# Break_Light_Schematic.net
KiCad netlist of a schematic drawn in Altium Designer
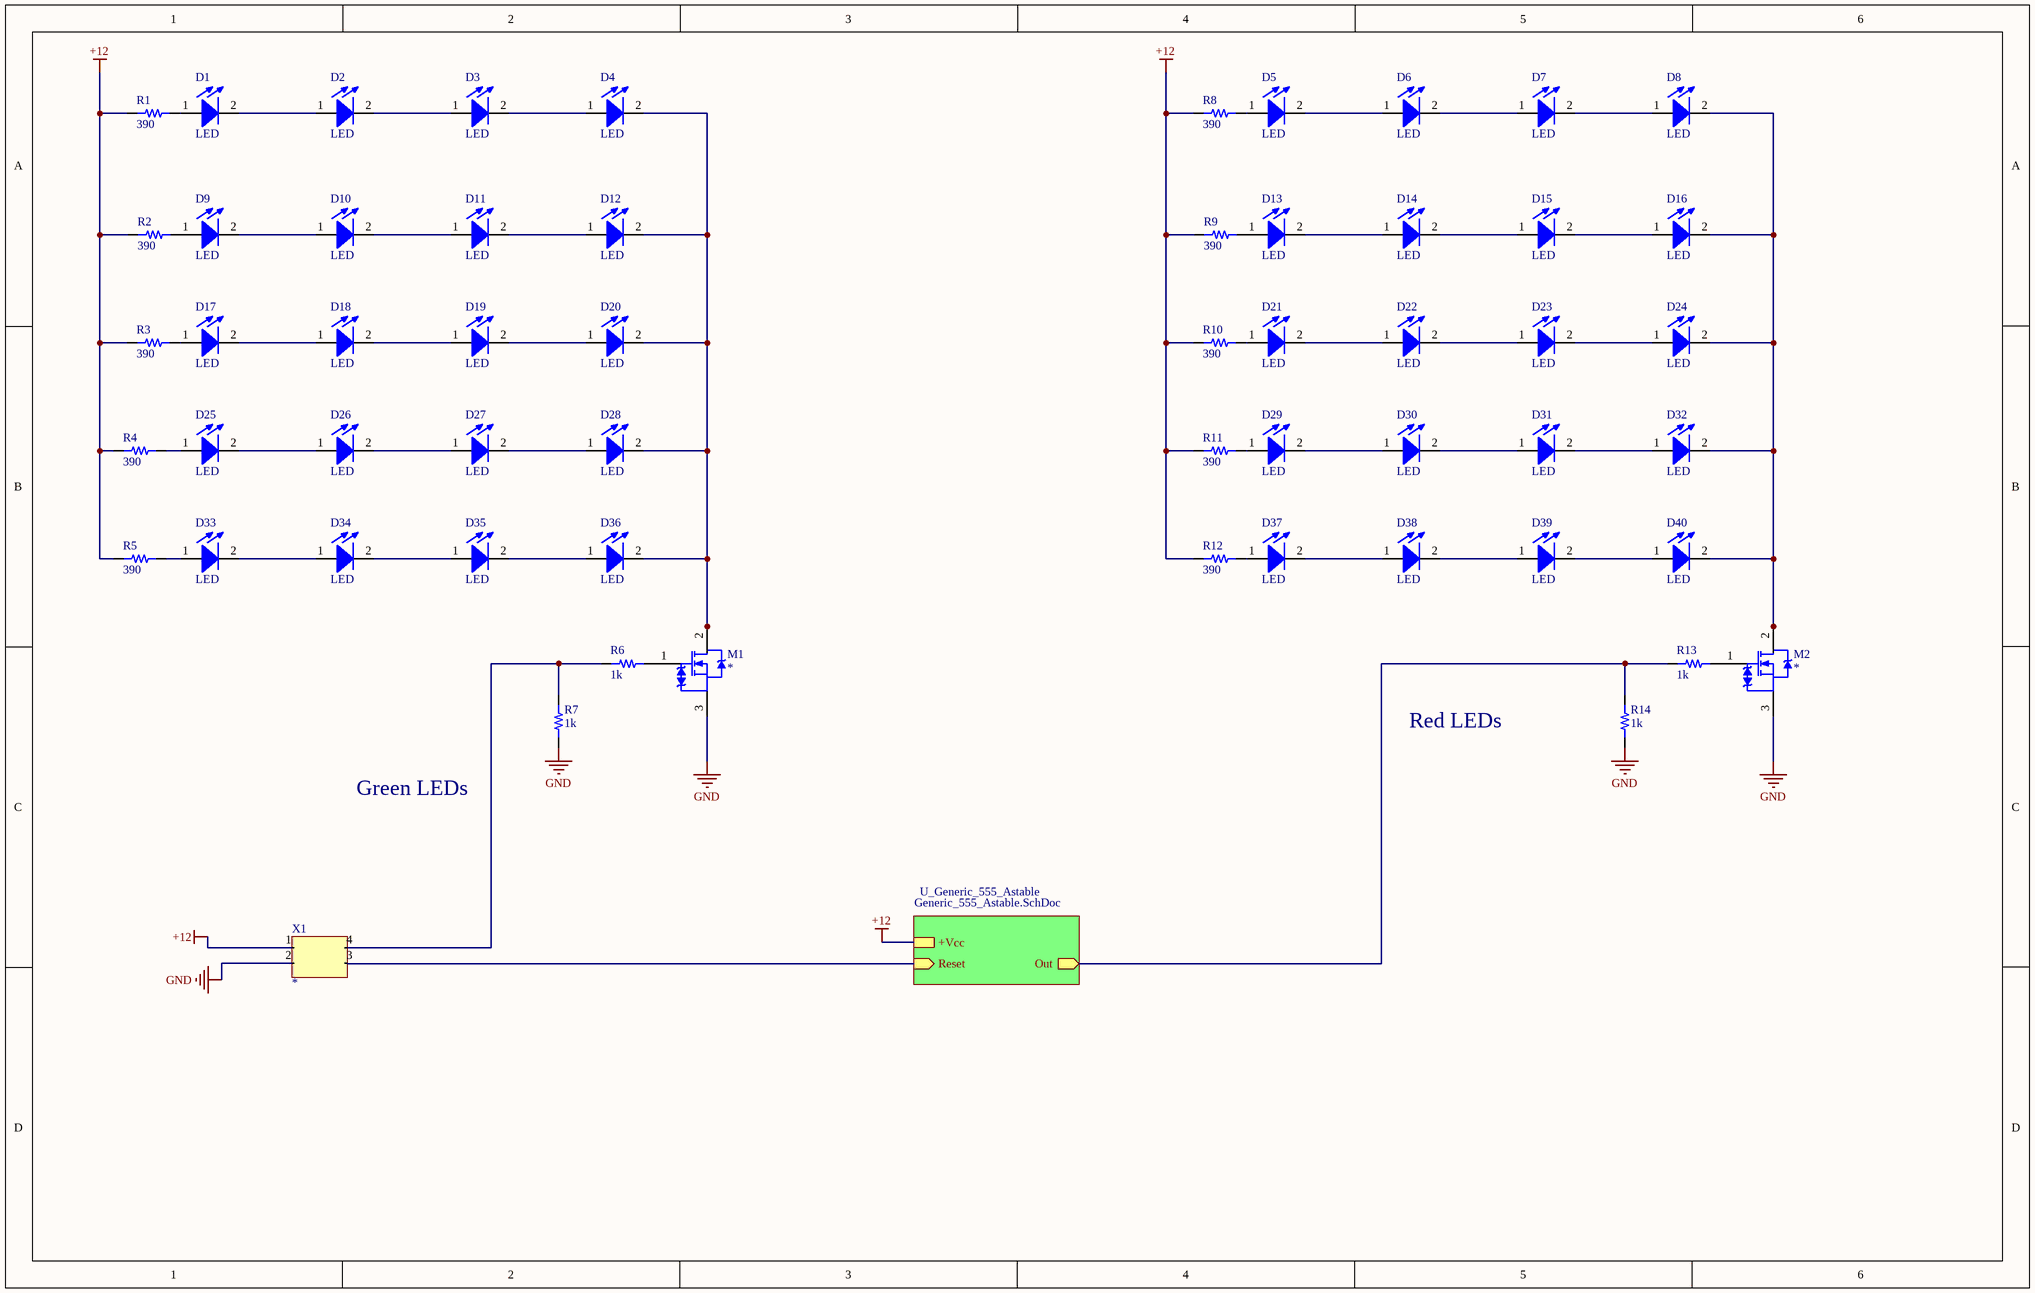
[diagram p0: Break Light Schematic.SchDoc]

(export (version "E")
  (design (tool "Eeschema 10.0.6"))
  (components
    (comp (ref "D1")
      (value "LED")
      (footprint "LED TH")
      (description "Thru Hole LED")
      (libsource (lib "altlib") (part "LED"))
    )
    (comp (ref "D2")
      (value "LED")
      (footprint "LED TH")
      (description "Thru Hole LED")
      (libsource (lib "altlib") (part "LED"))
    )
    (comp (ref "D3")
      (value "LED")
      (footprint "LED TH")
      (description "Thru Hole LED")
      (libsource (lib "altlib") (part "LED"))
    )
    (comp (ref "D4")
      (value "LED")
      (footprint "LED TH")
      (description "Thru Hole LED")
      (libsource (lib "altlib") (part "LED"))
    )
    (comp (ref "D5")
      (value "LED")
      (footprint "LED TH")
      (description "Thru Hole LED")
      (libsource (lib "altlib") (part "LED"))
    )
    (comp (ref "D6")
      (value "LED")
      (footprint "LED TH")
      (description "Thru Hole LED")
      (libsource (lib "altlib") (part "LED"))
    )
    (comp (ref "D7")
      (value "LED")
      (footprint "LED TH")
      (description "Thru Hole LED")
      (libsource (lib "altlib") (part "LED"))
    )
    (comp (ref "D8")
      (value "LED")
      (footprint "LED TH")
      (description "Thru Hole LED")
      (libsource (lib "altlib") (part "LED"))
    )
    (comp (ref "D9")
      (value "LED")
      (footprint "LED TH")
      (description "Thru Hole LED")
      (libsource (lib "altlib") (part "LED"))
    )
    (comp (ref "D10")
      (value "LED")
      (footprint "LED TH")
      (description "Thru Hole LED")
      (libsource (lib "altlib") (part "LED"))
    )
    (comp (ref "D11")
      (value "LED")
      (footprint "LED TH")
      (description "Thru Hole LED")
      (libsource (lib "altlib") (part "LED"))
    )
    (comp (ref "D12")
      (value "LED")
      (footprint "LED TH")
      (description "Thru Hole LED")
      (libsource (lib "altlib") (part "LED"))
    )
    (comp (ref "D13")
      (value "LED")
      (footprint "LED TH")
      (description "Thru Hole LED")
      (libsource (lib "altlib") (part "LED"))
    )
    (comp (ref "D14")
      (value "LED")
      (footprint "LED TH")
      (description "Thru Hole LED")
      (libsource (lib "altlib") (part "LED"))
    )
    (comp (ref "D15")
      (value "LED")
      (footprint "LED TH")
      (description "Thru Hole LED")
      (libsource (lib "altlib") (part "LED"))
    )
    (comp (ref "D16")
      (value "LED")
      (footprint "LED TH")
      (description "Thru Hole LED")
      (libsource (lib "altlib") (part "LED"))
    )
    (comp (ref "D17")
      (value "LED")
      (footprint "LED TH")
      (description "Thru Hole LED")
      (libsource (lib "altlib") (part "LED"))
    )
    (comp (ref "D18")
      (value "LED")
      (footprint "LED TH")
      (description "Thru Hole LED")
      (libsource (lib "altlib") (part "LED"))
    )
    (comp (ref "D19")
      (value "LED")
      (footprint "LED TH")
      (description "Thru Hole LED")
      (libsource (lib "altlib") (part "LED"))
    )
    (comp (ref "D20")
      (value "LED")
      (footprint "LED TH")
      (description "Thru Hole LED")
      (libsource (lib "altlib") (part "LED"))
    )
    (comp (ref "D21")
      (value "LED")
      (footprint "LED TH")
      (description "Thru Hole LED")
      (libsource (lib "altlib") (part "LED"))
    )
    (comp (ref "D22")
      (value "LED")
      (footprint "LED TH")
      (description "Thru Hole LED")
      (libsource (lib "altlib") (part "LED"))
    )
    (comp (ref "D23")
      (value "LED")
      (footprint "LED TH")
      (description "Thru Hole LED")
      (libsource (lib "altlib") (part "LED"))
    )
    (comp (ref "D24")
      (value "LED")
      (footprint "LED TH")
      (description "Thru Hole LED")
      (libsource (lib "altlib") (part "LED"))
    )
    (comp (ref "D25")
      (value "LED")
      (footprint "LED TH")
      (description "Thru Hole LED")
      (libsource (lib "altlib") (part "LED"))
    )
    (comp (ref "D26")
      (value "LED")
      (footprint "LED TH")
      (description "Thru Hole LED")
      (libsource (lib "altlib") (part "LED"))
    )
    (comp (ref "D27")
      (value "LED")
      (footprint "LED TH")
      (description "Thru Hole LED")
      (libsource (lib "altlib") (part "LED"))
    )
    (comp (ref "D28")
      (value "LED")
      (footprint "LED TH")
      (description "Thru Hole LED")
      (libsource (lib "altlib") (part "LED"))
    )
    (comp (ref "D29")
      (value "LED")
      (footprint "LED TH")
      (description "Thru Hole LED")
      (libsource (lib "altlib") (part "LED"))
    )
    (comp (ref "D30")
      (value "LED")
      (footprint "LED TH")
      (description "Thru Hole LED")
      (libsource (lib "altlib") (part "LED"))
    )
    (comp (ref "D31")
      (value "LED")
      (footprint "LED TH")
      (description "Thru Hole LED")
      (libsource (lib "altlib") (part "LED"))
    )
    (comp (ref "D32")
      (value "LED")
      (footprint "LED TH")
      (description "Thru Hole LED")
      (libsource (lib "altlib") (part "LED"))
    )
    (comp (ref "D33")
      (value "LED")
      (footprint "LED TH")
      (description "Thru Hole LED")
      (libsource (lib "altlib") (part "LED"))
    )
    (comp (ref "D34")
      (value "LED")
      (footprint "LED TH")
      (description "Thru Hole LED")
      (libsource (lib "altlib") (part "LED"))
    )
    (comp (ref "D35")
      (value "LED")
      (footprint "LED TH")
      (description "Thru Hole LED")
      (libsource (lib "altlib") (part "LED"))
    )
    (comp (ref "D36")
      (value "LED")
      (footprint "LED TH")
      (description "Thru Hole LED")
      (libsource (lib "altlib") (part "LED"))
    )
    (comp (ref "D37")
      (value "LED")
      (footprint "LED TH")
      (description "Thru Hole LED")
      (libsource (lib "altlib") (part "LED"))
    )
    (comp (ref "D38")
      (value "LED")
      (footprint "LED TH")
      (description "Thru Hole LED")
      (libsource (lib "altlib") (part "LED"))
    )
    (comp (ref "D39")
      (value "LED")
      (footprint "LED TH")
      (description "Thru Hole LED")
      (libsource (lib "altlib") (part "LED"))
    )
    (comp (ref "D40")
      (value "LED")
      (footprint "LED TH")
      (description "Thru Hole LED")
      (libsource (lib "altlib") (part "LED"))
    )
    (comp (ref "M1")
      (value "*")
      (footprint "SOT-223-3")
      (description "N-Channel 450V 600mA (Tc) 3W (Ta) Surface Mo")
      (libsource (lib "altlib") (part "STN3N45K3"))
    )
    (comp (ref "M2")
      (value "*")
      (footprint "SOT-223-3")
      (description "N-Channel 450V 600mA (Tc) 3W (Ta) Surface Mo")
      (libsource (lib "altlib") (part "STN3N45K3"))
    )
    (comp (ref "R1")
      (value "390")
      (footprint "RES 0603/1608")
      (fields (field (name "RESISTANCE") "390"))
      (libsource (lib "altlib") (part "Resistor"))
    )
    (comp (ref "R2")
      (value "390")
      (footprint "RES 0603/1608")
      (fields (field (name "RESISTANCE") "390"))
      (libsource (lib "altlib") (part "Resistor"))
    )
    (comp (ref "R3")
      (value "390")
      (footprint "RES 0603/1608")
      (fields (field (name "RESISTANCE") "390"))
      (libsource (lib "altlib") (part "Resistor"))
    )
    (comp (ref "R4")
      (value "390")
      (footprint "RES 0603/1608")
      (fields (field (name "RESISTANCE") "390"))
      (libsource (lib "altlib") (part "Resistor"))
    )
    (comp (ref "R5")
      (value "390")
      (footprint "RES 0603/1608")
      (fields (field (name "RESISTANCE") "390"))
      (libsource (lib "altlib") (part "Resistor"))
    )
    (comp (ref "R6")
      (value "1k")
      (footprint "RES 0603/1608")
      (fields (field (name "RESISTANCE") "1k"))
      (libsource (lib "altlib") (part "Resistor"))
    )
    (comp (ref "R7")
      (value "1k")
      (footprint "RES 0603/1608")
      (fields (field (name "RESISTANCE") "1k"))
      (libsource (lib "altlib") (part "Resistor"))
    )
    (comp (ref "R8")
      (value "390")
      (footprint "RES 0603/1608")
      (fields (field (name "RESISTANCE") "390"))
      (libsource (lib "altlib") (part "Resistor"))
    )
    (comp (ref "R9")
      (value "390")
      (footprint "RES 0603/1608")
      (fields (field (name "RESISTANCE") "390"))
      (libsource (lib "altlib") (part "Resistor"))
    )
    (comp (ref "R10")
      (value "390")
      (footprint "RES 0603/1608")
      (fields (field (name "RESISTANCE") "390"))
      (libsource (lib "altlib") (part "Resistor"))
    )
    (comp (ref "R11")
      (value "390")
      (footprint "RES 0603/1608")
      (fields (field (name "RESISTANCE") "390"))
      (libsource (lib "altlib") (part "Resistor"))
    )
    (comp (ref "R12")
      (value "390")
      (footprint "RES 0603/1608")
      (fields (field (name "RESISTANCE") "390"))
      (libsource (lib "altlib") (part "Resistor"))
    )
    (comp (ref "R13")
      (value "1k")
      (footprint "RES 0603/1608")
      (fields (field (name "RESISTANCE") "1k"))
      (libsource (lib "altlib") (part "Resistor"))
    )
    (comp (ref "R14")
      (value "1k")
      (footprint "RES 0603/1608")
      (fields (field (name "RESISTANCE") "1k"))
      (libsource (lib "altlib") (part "Resistor"))
    )
    (comp (ref "X1")
      (value "*")
      (footprint "DT15-4P")
      (description "DT15-4P Connector for Brakelight")
      (fields (field (name "CREATEDBY") "Andrew"))
      (libsource (lib "altlib") (part "CONN 4POS"))
    )
  )
  (nets
    (net (code "1") (name "+12") (class "Default")
      (node (ref "R1") (pin "1") (pinfunction "1_1") (pintype "passive"))
      (node (ref "R10") (pin "1") (pinfunction "1_1") (pintype "passive"))
      (node (ref "R11") (pin "1") (pinfunction "1_1") (pintype "passive"))
      (node (ref "R12") (pin "1") (pinfunction "1_1") (pintype "passive"))
      (node (ref "R2") (pin "1") (pinfunction "1_1") (pintype "passive"))
      (node (ref "R3") (pin "1") (pinfunction "1_1") (pintype "passive"))
      (node (ref "R4") (pin "1") (pinfunction "1_1") (pintype "passive"))
      (node (ref "R5") (pin "1") (pinfunction "1_1") (pintype "passive"))
      (node (ref "R8") (pin "1") (pinfunction "1_1") (pintype "passive"))
      (node (ref "R9") (pin "1") (pinfunction "1_1") (pintype "passive"))
      (node (ref "X1") (pin "1") (pintype "input"))
    )
    (net (code "2") (name "/Out") (class "Default")
      (node (ref "R13") (pin "1") (pinfunction "1_1") (pintype "passive"))
      (node (ref "R14") (pin "2") (pinfunction "2_2") (pintype "passive"))
    )
    (net (code "3") (name "/Reset") (class "Default") (node (ref "X1") (pin "3") (pintype "bidirectional")))
    (net (code "4") (name "GND") (class "Default")
      (node (ref "M1") (pin "3") (pinfunction "S_3") (pintype "passive"))
      (node (ref "M2") (pin "3") (pinfunction "S_3") (pintype "passive"))
      (node (ref "R14") (pin "1") (pinfunction "1_1") (pintype "passive"))
      (node (ref "R7") (pin "1") (pinfunction "1_1") (pintype "passive"))
      (node (ref "X1") (pin "2") (pintype "input"))
    )
    (net (code "5") (name "Net-(D1-A)") (class "Default")
      (node (ref "D1") (pin "1") (pinfunction "A_1") (pintype "passive"))
      (node (ref "R1") (pin "2") (pinfunction "2_2") (pintype "passive"))
    )
    (net (code "6") (name "Net-(D1-K)") (class "Default")
      (node (ref "D1") (pin "2") (pinfunction "K_2") (pintype "passive"))
      (node (ref "D2") (pin "1") (pinfunction "A_1") (pintype "passive"))
    )
    (net (code "7") (name "Net-(D2-K)") (class "Default")
      (node (ref "D2") (pin "2") (pinfunction "K_2") (pintype "passive"))
      (node (ref "D3") (pin "1") (pinfunction "A_1") (pintype "passive"))
    )
    (net (code "8") (name "Net-(D3-K)") (class "Default")
      (node (ref "D3") (pin "2") (pinfunction "K_2") (pintype "passive"))
      (node (ref "D4") (pin "1") (pinfunction "A_1") (pintype "passive"))
    )
    (net (code "9") (name "Net-(D5-A)") (class "Default")
      (node (ref "D5") (pin "1") (pinfunction "A_1") (pintype "passive"))
      (node (ref "R8") (pin "2") (pinfunction "2_2") (pintype "passive"))
    )
    (net (code "10") (name "Net-(D5-K)") (class "Default")
      (node (ref "D5") (pin "2") (pinfunction "K_2") (pintype "passive"))
      (node (ref "D6") (pin "1") (pinfunction "A_1") (pintype "passive"))
    )
    (net (code "11") (name "Net-(D6-K)") (class "Default")
      (node (ref "D6") (pin "2") (pinfunction "K_2") (pintype "passive"))
      (node (ref "D7") (pin "1") (pinfunction "A_1") (pintype "passive"))
    )
    (net (code "12") (name "Net-(D7-K)") (class "Default")
      (node (ref "D7") (pin "2") (pinfunction "K_2") (pintype "passive"))
      (node (ref "D8") (pin "1") (pinfunction "A_1") (pintype "passive"))
    )
    (net (code "13") (name "Net-(D9-A)") (class "Default")
      (node (ref "D9") (pin "1") (pinfunction "A_1") (pintype "passive"))
      (node (ref "R2") (pin "2") (pinfunction "2_2") (pintype "passive"))
    )
    (net (code "14") (name "Net-(D10-A)") (class "Default")
      (node (ref "D10") (pin "1") (pinfunction "A_1") (pintype "passive"))
      (node (ref "D9") (pin "2") (pinfunction "K_2") (pintype "passive"))
    )
    (net (code "15") (name "Net-(D10-K)") (class "Default")
      (node (ref "D10") (pin "2") (pinfunction "K_2") (pintype "passive"))
      (node (ref "D11") (pin "1") (pinfunction "A_1") (pintype "passive"))
    )
    (net (code "16") (name "Net-(D11-K)") (class "Default")
      (node (ref "D11") (pin "2") (pinfunction "K_2") (pintype "passive"))
      (node (ref "D12") (pin "1") (pinfunction "A_1") (pintype "passive"))
    )
    (net (code "17") (name "Net-(D12-K)") (class "Default")
      (node (ref "D12") (pin "2") (pinfunction "K_2") (pintype "passive"))
      (node (ref "D20") (pin "2") (pinfunction "K_2") (pintype "passive"))
      (node (ref "D28") (pin "2") (pinfunction "K_2") (pintype "passive"))
      (node (ref "D36") (pin "2") (pinfunction "K_2") (pintype "passive"))
      (node (ref "D4") (pin "2") (pinfunction "K_2") (pintype "passive"))
      (node (ref "M1") (pin "2") (pinfunction "D_2") (pintype "passive"))
      (node (ref "M1") (pin "THM") (pinfunction "D_THM") (pintype "passive"))
    )
    (net (code "18") (name "Net-(D13-A)") (class "Default")
      (node (ref "D13") (pin "1") (pinfunction "A_1") (pintype "passive"))
      (node (ref "R9") (pin "2") (pinfunction "2_2") (pintype "passive"))
    )
    (net (code "19") (name "Net-(D13-K)") (class "Default")
      (node (ref "D13") (pin "2") (pinfunction "K_2") (pintype "passive"))
      (node (ref "D14") (pin "1") (pinfunction "A_1") (pintype "passive"))
    )
    (net (code "20") (name "Net-(D14-K)") (class "Default")
      (node (ref "D14") (pin "2") (pinfunction "K_2") (pintype "passive"))
      (node (ref "D15") (pin "1") (pinfunction "A_1") (pintype "passive"))
    )
    (net (code "21") (name "Net-(D15-K)") (class "Default")
      (node (ref "D15") (pin "2") (pinfunction "K_2") (pintype "passive"))
      (node (ref "D16") (pin "1") (pinfunction "A_1") (pintype "passive"))
    )
    (net (code "22") (name "Net-(D16-K)") (class "Default")
      (node (ref "D16") (pin "2") (pinfunction "K_2") (pintype "passive"))
      (node (ref "D24") (pin "2") (pinfunction "K_2") (pintype "passive"))
      (node (ref "D32") (pin "2") (pinfunction "K_2") (pintype "passive"))
      (node (ref "D40") (pin "2") (pinfunction "K_2") (pintype "passive"))
      (node (ref "D8") (pin "2") (pinfunction "K_2") (pintype "passive"))
      (node (ref "M2") (pin "2") (pinfunction "D_2") (pintype "passive"))
      (node (ref "M2") (pin "THM") (pinfunction "D_THM") (pintype "passive"))
    )
    (net (code "23") (name "Net-(D17-A)") (class "Default")
      (node (ref "D17") (pin "1") (pinfunction "A_1") (pintype "passive"))
      (node (ref "R3") (pin "2") (pinfunction "2_2") (pintype "passive"))
    )
    (net (code "24") (name "Net-(D17-K)") (class "Default")
      (node (ref "D17") (pin "2") (pinfunction "K_2") (pintype "passive"))
      (node (ref "D18") (pin "1") (pinfunction "A_1") (pintype "passive"))
    )
    (net (code "25") (name "Net-(D18-K)") (class "Default")
      (node (ref "D18") (pin "2") (pinfunction "K_2") (pintype "passive"))
      (node (ref "D19") (pin "1") (pinfunction "A_1") (pintype "passive"))
    )
    (net (code "26") (name "Net-(D19-K)") (class "Default")
      (node (ref "D19") (pin "2") (pinfunction "K_2") (pintype "passive"))
      (node (ref "D20") (pin "1") (pinfunction "A_1") (pintype "passive"))
    )
    (net (code "27") (name "Net-(D21-A)") (class "Default")
      (node (ref "D21") (pin "1") (pinfunction "A_1") (pintype "passive"))
      (node (ref "R10") (pin "2") (pinfunction "2_2") (pintype "passive"))
    )
    (net (code "28") (name "Net-(D21-K)") (class "Default")
      (node (ref "D21") (pin "2") (pinfunction "K_2") (pintype "passive"))
      (node (ref "D22") (pin "1") (pinfunction "A_1") (pintype "passive"))
    )
    (net (code "29") (name "Net-(D22-K)") (class "Default")
      (node (ref "D22") (pin "2") (pinfunction "K_2") (pintype "passive"))
      (node (ref "D23") (pin "1") (pinfunction "A_1") (pintype "passive"))
    )
    (net (code "30") (name "Net-(D23-K)") (class "Default")
      (node (ref "D23") (pin "2") (pinfunction "K_2") (pintype "passive"))
      (node (ref "D24") (pin "1") (pinfunction "A_1") (pintype "passive"))
    )
    (net (code "31") (name "Net-(D25-A)") (class "Default")
      (node (ref "D25") (pin "1") (pinfunction "A_1") (pintype "passive"))
      (node (ref "R4") (pin "2") (pinfunction "2_2") (pintype "passive"))
    )
    (net (code "32") (name "Net-(D25-K)") (class "Default")
      (node (ref "D25") (pin "2") (pinfunction "K_2") (pintype "passive"))
      (node (ref "D26") (pin "1") (pinfunction "A_1") (pintype "passive"))
    )
    (net (code "33") (name "Net-(D26-K)") (class "Default")
      (node (ref "D26") (pin "2") (pinfunction "K_2") (pintype "passive"))
      (node (ref "D27") (pin "1") (pinfunction "A_1") (pintype "passive"))
    )
    (net (code "34") (name "Net-(D27-K)") (class "Default")
      (node (ref "D27") (pin "2") (pinfunction "K_2") (pintype "passive"))
      (node (ref "D28") (pin "1") (pinfunction "A_1") (pintype "passive"))
    )
    (net (code "35") (name "Net-(D29-A)") (class "Default")
      (node (ref "D29") (pin "1") (pinfunction "A_1") (pintype "passive"))
      (node (ref "R11") (pin "2") (pinfunction "2_2") (pintype "passive"))
    )
    (net (code "36") (name "Net-(D29-K)") (class "Default")
      (node (ref "D29") (pin "2") (pinfunction "K_2") (pintype "passive"))
      (node (ref "D30") (pin "1") (pinfunction "A_1") (pintype "passive"))
    )
    (net (code "37") (name "Net-(D30-K)") (class "Default")
      (node (ref "D30") (pin "2") (pinfunction "K_2") (pintype "passive"))
      (node (ref "D31") (pin "1") (pinfunction "A_1") (pintype "passive"))
    )
    (net (code "38") (name "Net-(D31-K)") (class "Default")
      (node (ref "D31") (pin "2") (pinfunction "K_2") (pintype "passive"))
      (node (ref "D32") (pin "1") (pinfunction "A_1") (pintype "passive"))
    )
    (net (code "39") (name "Net-(D33-A)") (class "Default")
      (node (ref "D33") (pin "1") (pinfunction "A_1") (pintype "passive"))
      (node (ref "R5") (pin "2") (pinfunction "2_2") (pintype "passive"))
    )
    (net (code "40") (name "Net-(D33-K)") (class "Default")
      (node (ref "D33") (pin "2") (pinfunction "K_2") (pintype "passive"))
      (node (ref "D34") (pin "1") (pinfunction "A_1") (pintype "passive"))
    )
    (net (code "41") (name "Net-(D34-K)") (class "Default")
      (node (ref "D34") (pin "2") (pinfunction "K_2") (pintype "passive"))
      (node (ref "D35") (pin "1") (pinfunction "A_1") (pintype "passive"))
    )
    (net (code "42") (name "Net-(D35-K)") (class "Default")
      (node (ref "D35") (pin "2") (pinfunction "K_2") (pintype "passive"))
      (node (ref "D36") (pin "1") (pinfunction "A_1") (pintype "passive"))
    )
    (net (code "43") (name "Net-(D37-A)") (class "Default")
      (node (ref "D37") (pin "1") (pinfunction "A_1") (pintype "passive"))
      (node (ref "R12") (pin "2") (pinfunction "2_2") (pintype "passive"))
    )
    (net (code "44") (name "Net-(D37-K)") (class "Default")
      (node (ref "D37") (pin "2") (pinfunction "K_2") (pintype "passive"))
      (node (ref "D38") (pin "1") (pinfunction "A_1") (pintype "passive"))
    )
    (net (code "45") (name "Net-(D38-K)") (class "Default")
      (node (ref "D38") (pin "2") (pinfunction "K_2") (pintype "passive"))
      (node (ref "D39") (pin "1") (pinfunction "A_1") (pintype "passive"))
    )
    (net (code "46") (name "Net-(D39-K)") (class "Default")
      (node (ref "D39") (pin "2") (pinfunction "K_2") (pintype "passive"))
      (node (ref "D40") (pin "1") (pinfunction "A_1") (pintype "passive"))
    )
    (net (code "47") (name "Net-(M1-G)") (class "Default")
      (node (ref "M1") (pin "1") (pinfunction "G_1") (pintype "passive"))
      (node (ref "R6") (pin "2") (pinfunction "2_2") (pintype "passive"))
    )
    (net (code "48") (name "Net-(M2-G)") (class "Default")
      (node (ref "M2") (pin "1") (pinfunction "G_1") (pintype "passive"))
      (node (ref "R13") (pin "2") (pinfunction "2_2") (pintype "passive"))
    )
    (net (code "49") (name "Net-(R6-Pad1)") (class "Default")
      (node (ref "R6") (pin "1") (pinfunction "1_1") (pintype "passive"))
      (node (ref "R7") (pin "2") (pinfunction "2_2") (pintype "passive"))
      (node (ref "X1") (pin "4") (pintype "input"))
    )
  )
)
